# HEADER_1.net
KiCad netlist of a schematic drawn in Altium Designer
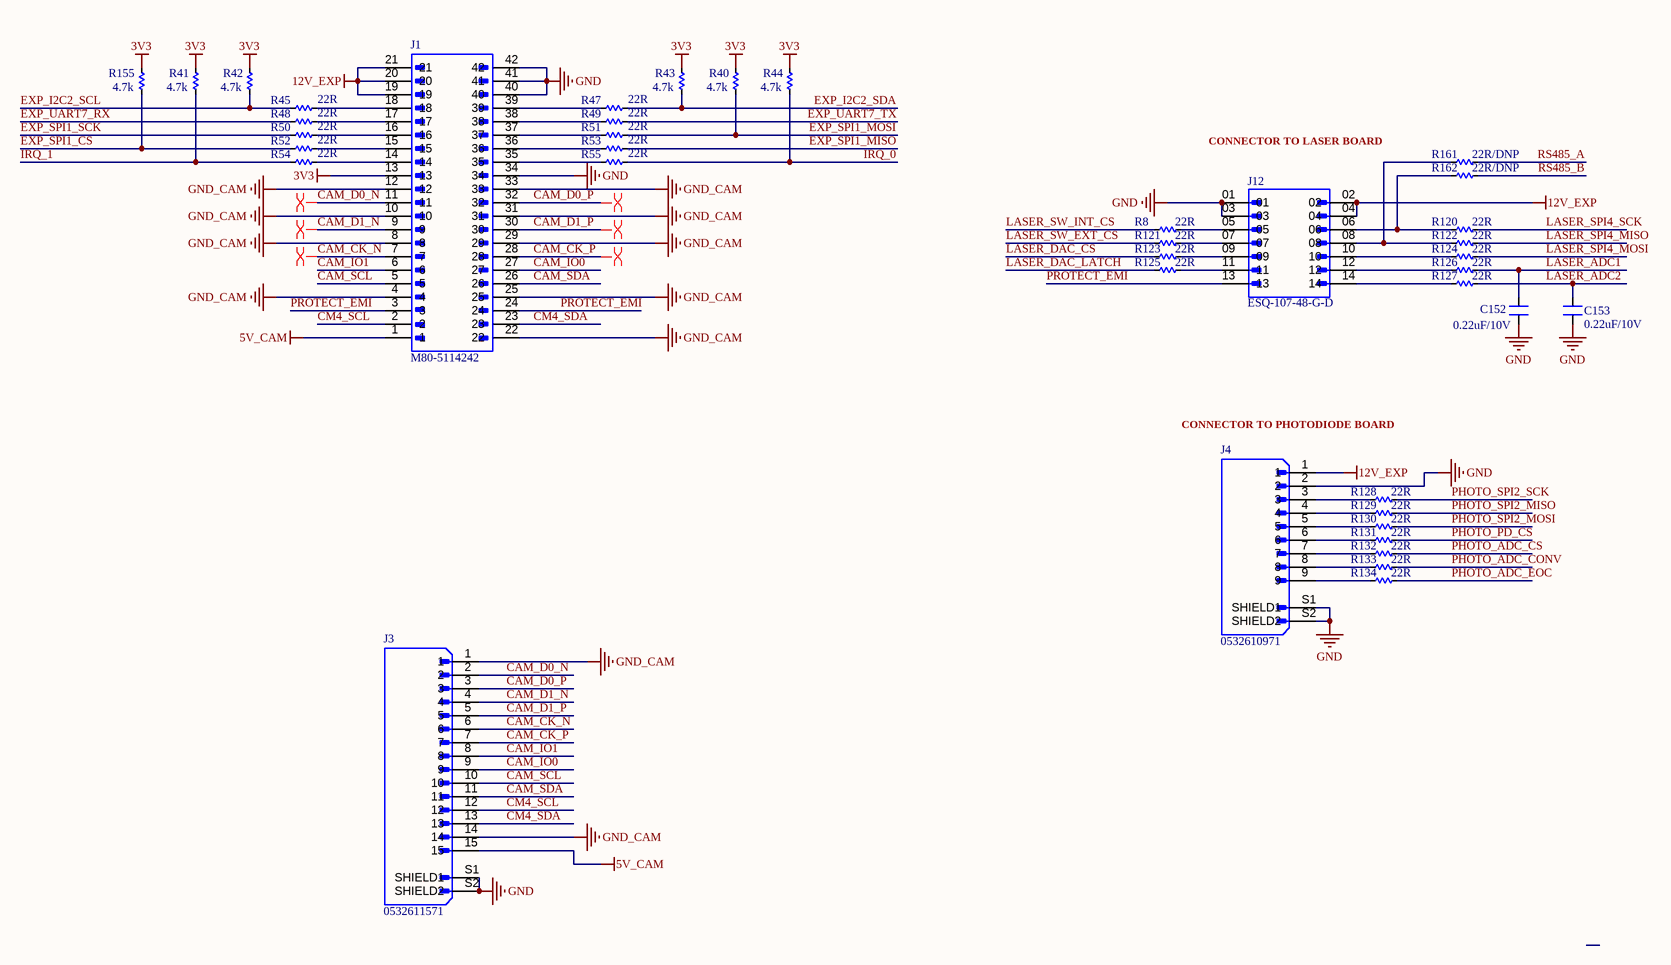
[diagram p0: HEADER_1.SchDoc]

(export (version "E")
  (design (tool "Eeschema 10.0.6"))
  (components
    (comp (ref "C152")
      (value "0.22uF/10V")
      (footprint "CAP_C_1608X80")
      (libsource (lib "EXP_HW_V3") (part "Capacitors"))
    )
    (comp (ref "C153")
      (value "0.22uF/10V")
      (footprint "CAP_C_1608X80")
      (libsource (lib "EXP_HW_V3") (part "Capacitors"))
    )
    (comp (ref "J1")
      (value "M80-5114242")
      (footprint "M80-5114242")
      (description "CONN HEADER VERT 42POS 2MM")
      (libsource (lib "EXP_HW_V2") (part "CONN_TH_42"))
    )
    (comp (ref "J3")
      (value "0532611571")
      (footprint "0532611571")
      (description "Conn Shrouded Header (4 Sides) HDR 15 POS 1.25mm Solder RA Side Entry SMD PicoBladeâ„¢ T/R")
      (fields (field (name "MP") "532611571") (field (name "MF") "Molex"))
      (libsource (lib "EXP_HW_V2") (part "CONN_SMD_15"))
    )
    (comp (ref "J4")
      (value "0532610971")
      (footprint "0532610971")
      (description "CONN HEADER SMD R/A 9POS 1.25MM")
      (libsource (lib "EXP_HW_V3") (part "CONN_SMD_09"))
    )
    (comp (ref "J12")
      (value "ESQ-107-48-G-D")
      (footprint "ESQ-107-37-G-D")
      (description "CONN SOCKET 14POS 0.1 GOLD PCB")
      (libsource (lib "EXP_HW_V2") (part "CONN_TH_14"))
    )
    (comp (ref "R8")
      (value "22R")
      (footprint "RES_C_1608X60")
      (description "SMD")
      (fields
        (field (name "MANUFACTURER") "Generic Components")
        (field (name "PUBLISHER") "Altium Hobart Technology Centre")
      )
      (libsource (lib "EXP_HW_V3") (part "Res SMD"))
    )
    (comp (ref "R40")
      (value "4.7k")
      (footprint "RES_C_1608X60")
      (description "SMD")
      (fields
        (field (name "MANUFACTURER") "Generic Components")
        (field (name "PUBLISHER") "Altium Hobart Technology Centre")
      )
      (libsource (lib "EXP_HW_V3") (part "Res SMD"))
    )
    (comp (ref "R41")
      (value "4.7k")
      (footprint "RES_C_1608X60")
      (description "SMD")
      (fields
        (field (name "MANUFACTURER") "Generic Components")
        (field (name "PUBLISHER") "Altium Hobart Technology Centre")
      )
      (libsource (lib "EXP_HW_V3") (part "Res SMD"))
    )
    (comp (ref "R42")
      (value "4.7k")
      (footprint "RES_C_1608X60")
      (description "SMD")
      (fields
        (field (name "MANUFACTURER") "Generic Components")
        (field (name "PUBLISHER") "Altium Hobart Technology Centre")
      )
      (libsource (lib "EXP_HW_V3") (part "Res SMD"))
    )
    (comp (ref "R43")
      (value "4.7k")
      (footprint "RES_C_1608X60")
      (description "SMD")
      (fields
        (field (name "MANUFACTURER") "Generic Components")
        (field (name "PUBLISHER") "Altium Hobart Technology Centre")
      )
      (libsource (lib "EXP_HW_V3") (part "Res SMD"))
    )
    (comp (ref "R44")
      (value "4.7k")
      (footprint "RES_C_1608X60")
      (description "SMD")
      (fields
        (field (name "MANUFACTURER") "Generic Components")
        (field (name "PUBLISHER") "Altium Hobart Technology Centre")
      )
      (libsource (lib "EXP_HW_V3") (part "Res SMD"))
    )
    (comp (ref "R45")
      (value "22R")
      (footprint "RES_C_1608X60")
      (description "SMD")
      (fields
        (field (name "MANUFACTURER") "Generic Components")
        (field (name "PUBLISHER") "Altium Hobart Technology Centre")
      )
      (libsource (lib "EXP_HW_V3") (part "Res SMD"))
    )
    (comp (ref "R47")
      (value "22R")
      (footprint "RES_C_1608X60")
      (description "SMD")
      (fields
        (field (name "MANUFACTURER") "Generic Components")
        (field (name "PUBLISHER") "Altium Hobart Technology Centre")
      )
      (libsource (lib "EXP_HW_V3") (part "Res SMD"))
    )
    (comp (ref "R48")
      (value "22R")
      (footprint "RES_C_1608X60")
      (description "SMD")
      (fields
        (field (name "MANUFACTURER") "Generic Components")
        (field (name "PUBLISHER") "Altium Hobart Technology Centre")
      )
      (libsource (lib "EXP_HW_V3") (part "Res SMD"))
    )
    (comp (ref "R49")
      (value "22R")
      (footprint "RES_C_1608X60")
      (description "SMD")
      (fields
        (field (name "MANUFACTURER") "Generic Components")
        (field (name "PUBLISHER") "Altium Hobart Technology Centre")
      )
      (libsource (lib "EXP_HW_V3") (part "Res SMD"))
    )
    (comp (ref "R50")
      (value "22R")
      (footprint "RES_C_1608X60")
      (description "SMD")
      (fields
        (field (name "MANUFACTURER") "Generic Components")
        (field (name "PUBLISHER") "Altium Hobart Technology Centre")
      )
      (libsource (lib "EXP_HW_V3") (part "Res SMD"))
    )
    (comp (ref "R51")
      (value "22R")
      (footprint "RES_C_1608X60")
      (description "SMD")
      (fields
        (field (name "MANUFACTURER") "Generic Components")
        (field (name "PUBLISHER") "Altium Hobart Technology Centre")
      )
      (libsource (lib "EXP_HW_V3") (part "Res SMD"))
    )
    (comp (ref "R52")
      (value "22R")
      (footprint "RES_C_1608X60")
      (description "SMD")
      (fields
        (field (name "MANUFACTURER") "Generic Components")
        (field (name "PUBLISHER") "Altium Hobart Technology Centre")
      )
      (libsource (lib "EXP_HW_V3") (part "Res SMD"))
    )
    (comp (ref "R53")
      (value "22R")
      (footprint "RES_C_1608X60")
      (description "SMD")
      (fields
        (field (name "MANUFACTURER") "Generic Components")
        (field (name "PUBLISHER") "Altium Hobart Technology Centre")
      )
      (libsource (lib "EXP_HW_V3") (part "Res SMD"))
    )
    (comp (ref "R54")
      (value "22R")
      (footprint "RES_C_1608X60")
      (description "SMD")
      (fields
        (field (name "MANUFACTURER") "Generic Components")
        (field (name "PUBLISHER") "Altium Hobart Technology Centre")
      )
      (libsource (lib "EXP_HW_V3") (part "Res SMD"))
    )
    (comp (ref "R55")
      (value "22R")
      (footprint "RES_C_1608X60")
      (description "SMD")
      (fields
        (field (name "MANUFACTURER") "Generic Components")
        (field (name "PUBLISHER") "Altium Hobart Technology Centre")
      )
      (libsource (lib "EXP_HW_V3") (part "Res SMD"))
    )
    (comp (ref "R120")
      (value "22R")
      (footprint "RES_C_1608X60")
      (description "SMD")
      (fields
        (field (name "MANUFACTURER") "Generic Components")
        (field (name "PUBLISHER") "Altium Hobart Technology Centre")
      )
      (libsource (lib "EXP_HW_V3") (part "Res SMD"))
    )
    (comp (ref "R121")
      (value "22R")
      (footprint "RES_C_1608X60")
      (description "SMD")
      (fields
        (field (name "MANUFACTURER") "Generic Components")
        (field (name "PUBLISHER") "Altium Hobart Technology Centre")
      )
      (libsource (lib "EXP_HW_V3") (part "Res SMD"))
    )
    (comp (ref "R122")
      (value "22R")
      (footprint "RES_C_1608X60")
      (description "SMD")
      (fields
        (field (name "MANUFACTURER") "Generic Components")
        (field (name "PUBLISHER") "Altium Hobart Technology Centre")
      )
      (libsource (lib "EXP_HW_V3") (part "Res SMD"))
    )
    (comp (ref "R123")
      (value "22R")
      (footprint "RES_C_1608X60")
      (description "SMD")
      (fields
        (field (name "MANUFACTURER") "Generic Components")
        (field (name "PUBLISHER") "Altium Hobart Technology Centre")
      )
      (libsource (lib "EXP_HW_V3") (part "Res SMD"))
    )
    (comp (ref "R124")
      (value "22R")
      (footprint "RES_C_1608X60")
      (description "SMD")
      (fields
        (field (name "MANUFACTURER") "Generic Components")
        (field (name "PUBLISHER") "Altium Hobart Technology Centre")
      )
      (libsource (lib "EXP_HW_V3") (part "Res SMD"))
    )
    (comp (ref "R125")
      (value "22R")
      (footprint "RES_C_1608X60")
      (description "SMD")
      (fields
        (field (name "MANUFACTURER") "Generic Components")
        (field (name "PUBLISHER") "Altium Hobart Technology Centre")
      )
      (libsource (lib "EXP_HW_V3") (part "Res SMD"))
    )
    (comp (ref "R126")
      (value "22R")
      (footprint "RES_C_1608X60")
      (description "SMD")
      (fields
        (field (name "MANUFACTURER") "Generic Components")
        (field (name "PUBLISHER") "Altium Hobart Technology Centre")
      )
      (libsource (lib "EXP_HW_V3") (part "Res SMD"))
    )
    (comp (ref "R127")
      (value "22R")
      (footprint "RES_C_1608X60")
      (description "SMD")
      (fields
        (field (name "MANUFACTURER") "Generic Components")
        (field (name "PUBLISHER") "Altium Hobart Technology Centre")
      )
      (libsource (lib "EXP_HW_V3") (part "Res SMD"))
    )
    (comp (ref "R128")
      (value "22R")
      (footprint "RES_C_1608X60")
      (description "SMD")
      (fields
        (field (name "MANUFACTURER") "Generic Components")
        (field (name "PUBLISHER") "Altium Hobart Technology Centre")
      )
      (libsource (lib "EXP_HW_V3") (part "Res SMD"))
    )
    (comp (ref "R129")
      (value "22R")
      (footprint "RES_C_1608X60")
      (description "SMD")
      (fields
        (field (name "MANUFACTURER") "Generic Components")
        (field (name "PUBLISHER") "Altium Hobart Technology Centre")
      )
      (libsource (lib "EXP_HW_V3") (part "Res SMD"))
    )
    (comp (ref "R130")
      (value "22R")
      (footprint "RES_C_1608X60")
      (description "SMD")
      (fields
        (field (name "MANUFACTURER") "Generic Components")
        (field (name "PUBLISHER") "Altium Hobart Technology Centre")
      )
      (libsource (lib "EXP_HW_V3") (part "Res SMD"))
    )
    (comp (ref "R131")
      (value "22R")
      (footprint "RES_C_1608X60")
      (description "SMD")
      (fields
        (field (name "MANUFACTURER") "Generic Components")
        (field (name "PUBLISHER") "Altium Hobart Technology Centre")
      )
      (libsource (lib "EXP_HW_V3") (part "Res SMD"))
    )
    (comp (ref "R132")
      (value "22R")
      (footprint "RES_C_1608X60")
      (description "SMD")
      (fields
        (field (name "MANUFACTURER") "Generic Components")
        (field (name "PUBLISHER") "Altium Hobart Technology Centre")
      )
      (libsource (lib "EXP_HW_V3") (part "Res SMD"))
    )
    (comp (ref "R133")
      (value "22R")
      (footprint "RES_C_1608X60")
      (description "SMD")
      (fields
        (field (name "MANUFACTURER") "Generic Components")
        (field (name "PUBLISHER") "Altium Hobart Technology Centre")
      )
      (libsource (lib "EXP_HW_V3") (part "Res SMD"))
    )
    (comp (ref "R134")
      (value "22R")
      (footprint "RES_C_1608X60")
      (description "SMD")
      (fields
        (field (name "MANUFACTURER") "Generic Components")
        (field (name "PUBLISHER") "Altium Hobart Technology Centre")
      )
      (libsource (lib "EXP_HW_V3") (part "Res SMD"))
    )
    (comp (ref "R155")
      (value "4.7k")
      (footprint "RES_C_1608X60")
      (description "SMD")
      (fields
        (field (name "MANUFACTURER") "Generic Components")
        (field (name "PUBLISHER") "Altium Hobart Technology Centre")
      )
      (libsource (lib "EXP_HW_V3") (part "Res SMD"))
    )
    (comp (ref "R161")
      (value "22R/DNP")
      (footprint "RES_C_1608X60")
      (description "SMD")
      (fields
        (field (name "MANUFACTURER") "Generic Components")
        (field (name "PUBLISHER") "Altium Hobart Technology Centre")
      )
      (libsource (lib "EXP_HW_V3") (part "Res SMD"))
    )
    (comp (ref "R162")
      (value "22R/DNP")
      (footprint "RES_C_1608X60")
      (description "SMD")
      (fields
        (field (name "MANUFACTURER") "Generic Components")
        (field (name "PUBLISHER") "Altium Hobart Technology Centre")
      )
      (libsource (lib "EXP_HW_V3") (part "Res SMD"))
    )
  )
  (nets
    (net (code "1") (name "/CAM_CK_N") (class "Default")
      (node (ref "J1") (pin "7") (pinfunction "7_7") (pintype "passive"))
      (node (ref "J3") (pin "6") (pinfunction "6_6") (pintype "passive"))
    )
    (net (code "2") (name "/CAM_CK_P") (class "Default")
      (node (ref "J1") (pin "28") (pinfunction "28_28") (pintype "passive"))
      (node (ref "J3") (pin "7") (pinfunction "7_7") (pintype "passive"))
    )
    (net (code "3") (name "/CAM_D0_N") (class "Default")
      (node (ref "J1") (pin "11") (pinfunction "11_11") (pintype "passive"))
      (node (ref "J3") (pin "2") (pinfunction "2_2") (pintype "passive"))
    )
    (net (code "4") (name "/CAM_D0_P") (class "Default")
      (node (ref "J1") (pin "32") (pinfunction "32_32") (pintype "passive"))
      (node (ref "J3") (pin "3") (pinfunction "3_3") (pintype "passive"))
    )
    (net (code "5") (name "/CAM_D1_N") (class "Default")
      (node (ref "J1") (pin "9") (pinfunction "9_9") (pintype "passive"))
      (node (ref "J3") (pin "4") (pinfunction "4_4") (pintype "passive"))
    )
    (net (code "6") (name "/CAM_D1_P") (class "Default")
      (node (ref "J1") (pin "30") (pinfunction "30_30") (pintype "passive"))
      (node (ref "J3") (pin "5") (pinfunction "5_5") (pintype "passive"))
    )
    (net (code "7") (name "/CAM_IO0") (class "Default")
      (node (ref "J1") (pin "27") (pinfunction "27_27") (pintype "passive"))
      (node (ref "J3") (pin "9") (pinfunction "9_9") (pintype "passive"))
    )
    (net (code "8") (name "/CAM_IO1") (class "Default")
      (node (ref "J1") (pin "6") (pinfunction "6_6") (pintype "passive"))
      (node (ref "J3") (pin "8") (pinfunction "8_8") (pintype "passive"))
    )
    (net (code "9") (name "/CAM_SCL") (class "Default")
      (node (ref "J1") (pin "5") (pinfunction "5_5") (pintype "passive"))
      (node (ref "J3") (pin "10") (pinfunction "10_10") (pintype "passive"))
    )
    (net (code "10") (name "/CAM_SDA") (class "Default")
      (node (ref "J1") (pin "26") (pinfunction "26_26") (pintype "passive"))
      (node (ref "J3") (pin "11") (pinfunction "11_11") (pintype "passive"))
    )
    (net (code "11") (name "/CM4_SCL") (class "Default")
      (node (ref "J1") (pin "2") (pinfunction "2_2") (pintype "passive"))
      (node (ref "J3") (pin "12") (pinfunction "12_12") (pintype "passive"))
    )
    (net (code "12") (name "/CM4_SDA") (class "Default")
      (node (ref "J1") (pin "23") (pinfunction "23_23") (pintype "passive"))
      (node (ref "J3") (pin "13") (pinfunction "13_13") (pintype "passive"))
    )
    (net (code "13") (name "/EXP_I2C2_SCL") (class "Default")
      (node (ref "R42") (pin "2") (pinfunction "2_2") (pintype "passive"))
      (node (ref "R45") (pin "1") (pinfunction "1_1") (pintype "passive"))
    )
    (net (code "14") (name "/EXP_I2C2_SDA") (class "Default")
      (node (ref "R43") (pin "2") (pinfunction "2_2") (pintype "passive"))
      (node (ref "R47") (pin "2") (pinfunction "2_2") (pintype "passive"))
    )
    (net (code "15") (name "/EXP_SPI1_CS") (class "Default")
      (node (ref "R155") (pin "2") (pinfunction "2_2") (pintype "passive"))
      (node (ref "R52") (pin "1") (pinfunction "1_1") (pintype "passive"))
    )
    (net (code "16") (name "/EXP_SPI1_MISO") (class "Default")
      (node (ref "R53") (pin "2") (pinfunction "2_2") (pintype "passive"))
    )
    (net (code "17") (name "/EXP_SPI1_MOSI") (class "Default")
      (node (ref "R40") (pin "2") (pinfunction "2_2") (pintype "passive"))
      (node (ref "R51") (pin "2") (pinfunction "2_2") (pintype "passive"))
    )
    (net (code "18") (name "/EXP_SPI1_SCK") (class "Default")
      (node (ref "R50") (pin "1") (pinfunction "1_1") (pintype "passive"))
    )
    (net (code "19") (name "/EXP_UART7_RX") (class "Default")
      (node (ref "R48") (pin "1") (pinfunction "1_1") (pintype "passive"))
    )
    (net (code "20") (name "/EXP_UART7_TX") (class "Default")
      (node (ref "R49") (pin "2") (pinfunction "2_2") (pintype "passive"))
    )
    (net (code "21") (name "/IRQ_0") (class "Default")
      (node (ref "R44") (pin "2") (pinfunction "2_2") (pintype "passive"))
      (node (ref "R55") (pin "2") (pinfunction "2_2") (pintype "passive"))
    )
    (net (code "22") (name "/IRQ_1") (class "Default")
      (node (ref "R41") (pin "2") (pinfunction "2_2") (pintype "passive"))
      (node (ref "R54") (pin "1") (pinfunction "1_1") (pintype "passive"))
    )
    (net (code "23") (name "/LASER_ADC1") (class "Default")
      (node (ref "C152") (pin "2") (pinfunction "2_2") (pintype "passive"))
      (node (ref "R126") (pin "2") (pinfunction "2_2") (pintype "passive"))
    )
    (net (code "24") (name "/LASER_ADC2") (class "Default")
      (node (ref "C153") (pin "2") (pinfunction "2_2") (pintype "passive"))
      (node (ref "R127") (pin "2") (pinfunction "2_2") (pintype "passive"))
    )
    (net (code "25") (name "/LASER_DAC_CS") (class "Default")
      (node (ref "R123") (pin "1") (pinfunction "1_1") (pintype "passive"))
    )
    (net (code "26") (name "/LASER_DAC_LATCH") (class "Default")
      (node (ref "R125") (pin "1") (pinfunction "1_1") (pintype "passive"))
    )
    (net (code "27") (name "/LASER_SPI4_MISO") (class "Default")
      (node (ref "R122") (pin "2") (pinfunction "2_2") (pintype "passive"))
    )
    (net (code "28") (name "/LASER_SPI4_MOSI") (class "Default")
      (node (ref "R124") (pin "2") (pinfunction "2_2") (pintype "passive"))
    )
    (net (code "29") (name "/LASER_SPI4_SCK") (class "Default")
      (node (ref "R120") (pin "2") (pinfunction "2_2") (pintype "passive"))
    )
    (net (code "30") (name "/LASER_SW_EXT_CS") (class "Default")
      (node (ref "R121") (pin "1") (pinfunction "1_1") (pintype "passive"))
    )
    (net (code "31") (name "/LASER_SW_INT_CS") (class "Default")
      (node (ref "R8") (pin "1") (pinfunction "1_1") (pintype "passive"))
    )
    (net (code "32") (name "/PHOTO_ADC_CONV") (class "Default")
      (node (ref "R133") (pin "2") (pinfunction "2_2") (pintype "passive"))
    )
    (net (code "33") (name "/PHOTO_ADC_CS") (class "Default")
      (node (ref "R132") (pin "2") (pinfunction "2_2") (pintype "passive"))
    )
    (net (code "34") (name "/PHOTO_ADC_EOC") (class "Default")
      (node (ref "R134") (pin "2") (pinfunction "2_2") (pintype "passive"))
    )
    (net (code "35") (name "/PHOTO_PD_CS") (class "Default")
      (node (ref "R131") (pin "2") (pinfunction "2_2") (pintype "passive"))
    )
    (net (code "36") (name "/PHOTO_SPI2_MISO") (class "Default")
      (node (ref "R129") (pin "2") (pinfunction "2_2") (pintype "passive"))
    )
    (net (code "37") (name "/PHOTO_SPI2_MOSI") (class "Default")
      (node (ref "R130") (pin "2") (pinfunction "2_2") (pintype "passive"))
    )
    (net (code "38") (name "/PHOTO_SPI2_SCK") (class "Default")
      (node (ref "R128") (pin "2") (pinfunction "2_2") (pintype "passive"))
    )
    (net (code "39") (name "/PROTECT_EMI") (class "Default")
      (node (ref "J1") (pin "24") (pinfunction "24_24") (pintype "passive"))
      (node (ref "J1") (pin "3") (pinfunction "3_3") (pintype "passive"))
      (node (ref "J12") (pin "13") (pinfunction "13_13") (pintype "passive"))
    )
    (net (code "40") (name "/RS485_A") (class "Default")
      (node (ref "R161") (pin "2") (pinfunction "2_2") (pintype "passive"))
    )
    (net (code "41") (name "/RS485_B") (class "Default")
      (node (ref "R162") (pin "2") (pinfunction "2_2") (pintype "passive"))
    )
    (net (code "42") (name "3V3") (class "Default")
      (node (ref "J1") (pin "13") (pinfunction "13_13") (pintype "passive"))
      (node (ref "R155") (pin "1") (pinfunction "1_1") (pintype "passive"))
      (node (ref "R40") (pin "1") (pinfunction "1_1") (pintype "passive"))
      (node (ref "R41") (pin "1") (pinfunction "1_1") (pintype "passive"))
      (node (ref "R42") (pin "1") (pinfunction "1_1") (pintype "passive"))
      (node (ref "R43") (pin "1") (pinfunction "1_1") (pintype "passive"))
      (node (ref "R44") (pin "1") (pinfunction "1_1") (pintype "passive"))
    )
    (net (code "43") (name "5V_CAM") (class "Default")
      (node (ref "J1") (pin "1") (pinfunction "1_1") (pintype "passive"))
      (node (ref "J3") (pin "15") (pinfunction "15_15") (pintype "passive"))
    )
    (net (code "44") (name "12V_EXP") (class "Default")
      (node (ref "J1") (pin "19") (pinfunction "19_19") (pintype "passive"))
      (node (ref "J1") (pin "20") (pinfunction "20_20") (pintype "passive"))
      (node (ref "J1") (pin "21") (pinfunction "21_21") (pintype "passive"))
      (node (ref "J12") (pin "02") (pinfunction "02_02") (pintype "passive"))
      (node (ref "J12") (pin "04") (pinfunction "04_04") (pintype "passive"))
      (node (ref "J4") (pin "1") (pinfunction "1_1") (pintype "passive"))
    )
    (net (code "45") (name "GND") (class "Default")
      (node (ref "C152") (pin "1") (pinfunction "1_1") (pintype "passive"))
      (node (ref "C153") (pin "1") (pinfunction "1_1") (pintype "passive"))
      (node (ref "J1") (pin "34") (pinfunction "34_34") (pintype "passive"))
      (node (ref "J1") (pin "40") (pinfunction "40_40") (pintype "passive"))
      (node (ref "J1") (pin "41") (pinfunction "41_41") (pintype "passive"))
      (node (ref "J1") (pin "42") (pinfunction "42_42") (pintype "passive"))
      (node (ref "J12") (pin "01") (pinfunction "01_01") (pintype "passive"))
      (node (ref "J12") (pin "03") (pinfunction "03_03") (pintype "passive"))
      (node (ref "J3") (pin "S1") (pinfunction "SHIELD1_S1") (pintype "passive"))
      (node (ref "J3") (pin "S2") (pinfunction "SHIELD2_S2") (pintype "passive"))
      (node (ref "J4") (pin "2") (pinfunction "2_2") (pintype "passive"))
      (node (ref "J4") (pin "S1") (pinfunction "SHIELD1_S1") (pintype "passive"))
      (node (ref "J4") (pin "S2") (pinfunction "SHIELD2_S2") (pintype "passive"))
    )
    (net (code "46") (name "GND_CAM") (class "Default")
      (node (ref "J1") (pin "10") (pinfunction "10_10") (pintype "passive"))
      (node (ref "J1") (pin "12") (pinfunction "12_12") (pintype "passive"))
      (node (ref "J1") (pin "22") (pinfunction "22_22") (pintype "passive"))
      (node (ref "J1") (pin "25") (pinfunction "25_25") (pintype "passive"))
      (node (ref "J1") (pin "29") (pinfunction "29_29") (pintype "passive"))
      (node (ref "J1") (pin "31") (pinfunction "31_31") (pintype "passive"))
      (node (ref "J1") (pin "33") (pinfunction "33_33") (pintype "passive"))
      (node (ref "J1") (pin "4") (pinfunction "4_4") (pintype "passive"))
      (node (ref "J1") (pin "8") (pinfunction "8_8") (pintype "passive"))
      (node (ref "J3") (pin "1") (pinfunction "1_1") (pintype "passive"))
      (node (ref "J3") (pin "14") (pinfunction "14_14") (pintype "passive"))
    )
    (net (code "47") (name "Net-(J1-Pad14)") (class "Default")
      (node (ref "J1") (pin "14") (pinfunction "14_14") (pintype "passive"))
      (node (ref "R54") (pin "2") (pinfunction "2_2") (pintype "passive"))
    )
    (net (code "48") (name "Net-(J1-Pad15)") (class "Default")
      (node (ref "J1") (pin "15") (pinfunction "15_15") (pintype "passive"))
      (node (ref "R52") (pin "2") (pinfunction "2_2") (pintype "passive"))
    )
    (net (code "49") (name "Net-(J1-Pad16)") (class "Default")
      (node (ref "J1") (pin "16") (pinfunction "16_16") (pintype "passive"))
      (node (ref "R50") (pin "2") (pinfunction "2_2") (pintype "passive"))
    )
    (net (code "50") (name "Net-(J1-Pad17)") (class "Default")
      (node (ref "J1") (pin "17") (pinfunction "17_17") (pintype "passive"))
      (node (ref "R48") (pin "2") (pinfunction "2_2") (pintype "passive"))
    )
    (net (code "51") (name "Net-(J1-Pad18)") (class "Default")
      (node (ref "J1") (pin "18") (pinfunction "18_18") (pintype "passive"))
      (node (ref "R45") (pin "2") (pinfunction "2_2") (pintype "passive"))
    )
    (net (code "52") (name "Net-(J1-Pad35)") (class "Default")
      (node (ref "J1") (pin "35") (pinfunction "35_35") (pintype "passive"))
      (node (ref "R55") (pin "1") (pinfunction "1_1") (pintype "passive"))
    )
    (net (code "53") (name "Net-(J1-Pad36)") (class "Default")
      (node (ref "J1") (pin "36") (pinfunction "36_36") (pintype "passive"))
      (node (ref "R53") (pin "1") (pinfunction "1_1") (pintype "passive"))
    )
    (net (code "54") (name "Net-(J1-Pad37)") (class "Default")
      (node (ref "J1") (pin "37") (pinfunction "37_37") (pintype "passive"))
      (node (ref "R51") (pin "1") (pinfunction "1_1") (pintype "passive"))
    )
    (net (code "55") (name "Net-(J1-Pad38)") (class "Default")
      (node (ref "J1") (pin "38") (pinfunction "38_38") (pintype "passive"))
      (node (ref "R49") (pin "1") (pinfunction "1_1") (pintype "passive"))
    )
    (net (code "56") (name "Net-(J1-Pad39)") (class "Default")
      (node (ref "J1") (pin "39") (pinfunction "39_39") (pintype "passive"))
      (node (ref "R47") (pin "1") (pinfunction "1_1") (pintype "passive"))
    )
    (net (code "57") (name "Net-(J4-Pad3)") (class "Default")
      (node (ref "J4") (pin "3") (pinfunction "3_3") (pintype "passive"))
      (node (ref "R128") (pin "1") (pinfunction "1_1") (pintype "passive"))
    )
    (net (code "58") (name "Net-(J4-Pad4)") (class "Default")
      (node (ref "J4") (pin "4") (pinfunction "4_4") (pintype "passive"))
      (node (ref "R129") (pin "1") (pinfunction "1_1") (pintype "passive"))
    )
    (net (code "59") (name "Net-(J4-Pad5)") (class "Default")
      (node (ref "J4") (pin "5") (pinfunction "5_5") (pintype "passive"))
      (node (ref "R130") (pin "1") (pinfunction "1_1") (pintype "passive"))
    )
    (net (code "60") (name "Net-(J4-Pad6)") (class "Default")
      (node (ref "J4") (pin "6") (pinfunction "6_6") (pintype "passive"))
      (node (ref "R131") (pin "1") (pinfunction "1_1") (pintype "passive"))
    )
    (net (code "61") (name "Net-(J4-Pad7)") (class "Default")
      (node (ref "J4") (pin "7") (pinfunction "7_7") (pintype "passive"))
      (node (ref "R132") (pin "1") (pinfunction "1_1") (pintype "passive"))
    )
    (net (code "62") (name "Net-(J4-Pad8)") (class "Default")
      (node (ref "J4") (pin "8") (pinfunction "8_8") (pintype "passive"))
      (node (ref "R133") (pin "1") (pinfunction "1_1") (pintype "passive"))
    )
    (net (code "63") (name "Net-(J4-Pad9)") (class "Default")
      (node (ref "J4") (pin "9") (pinfunction "9_9") (pintype "passive"))
      (node (ref "R134") (pin "1") (pinfunction "1_1") (pintype "passive"))
    )
    (net (code "64") (name "Net-(J12-Pad05)") (class "Default")
      (node (ref "J12") (pin "05") (pinfunction "05_05") (pintype "passive"))
      (node (ref "R8") (pin "2") (pinfunction "2_2") (pintype "passive"))
    )
    (net (code "65") (name "Net-(J12-Pad06)") (class "Default")
      (node (ref "J12") (pin "06") (pinfunction "06_06") (pintype "passive"))
      (node (ref "R120") (pin "1") (pinfunction "1_1") (pintype "passive"))
      (node (ref "R162") (pin "1") (pinfunction "1_1") (pintype "passive"))
    )
    (net (code "66") (name "Net-(J12-Pad07)") (class "Default")
      (node (ref "J12") (pin "07") (pinfunction "07_07") (pintype "passive"))
      (node (ref "R121") (pin "2") (pinfunction "2_2") (pintype "passive"))
    )
    (net (code "67") (name "Net-(J12-Pad08)") (class "Default")
      (node (ref "J12") (pin "08") (pinfunction "08_08") (pintype "passive"))
      (node (ref "R122") (pin "1") (pinfunction "1_1") (pintype "passive"))
      (node (ref "R161") (pin "1") (pinfunction "1_1") (pintype "passive"))
    )
    (net (code "68") (name "Net-(J12-Pad09)") (class "Default")
      (node (ref "J12") (pin "09") (pinfunction "09_09") (pintype "passive"))
      (node (ref "R123") (pin "2") (pinfunction "2_2") (pintype "passive"))
    )
    (net (code "69") (name "Net-(J12-Pad10)") (class "Default")
      (node (ref "J12") (pin "10") (pinfunction "10_10") (pintype "passive"))
      (node (ref "R124") (pin "1") (pinfunction "1_1") (pintype "passive"))
    )
    (net (code "70") (name "Net-(J12-Pad11)") (class "Default")
      (node (ref "J12") (pin "11") (pinfunction "11_11") (pintype "passive"))
      (node (ref "R125") (pin "2") (pinfunction "2_2") (pintype "passive"))
    )
    (net (code "71") (name "Net-(J12-Pad12)") (class "Default")
      (node (ref "J12") (pin "12") (pinfunction "12_12") (pintype "passive"))
      (node (ref "R126") (pin "1") (pinfunction "1_1") (pintype "passive"))
    )
    (net (code "72") (name "Net-(J12-Pad14)") (class "Default")
      (node (ref "J12") (pin "14") (pinfunction "14_14") (pintype "passive"))
      (node (ref "R127") (pin "1") (pinfunction "1_1") (pintype "passive"))
    )
  )
)
